# Sheet_Multivibrator.net
KiCad netlist of a schematic drawn in Altium Designer
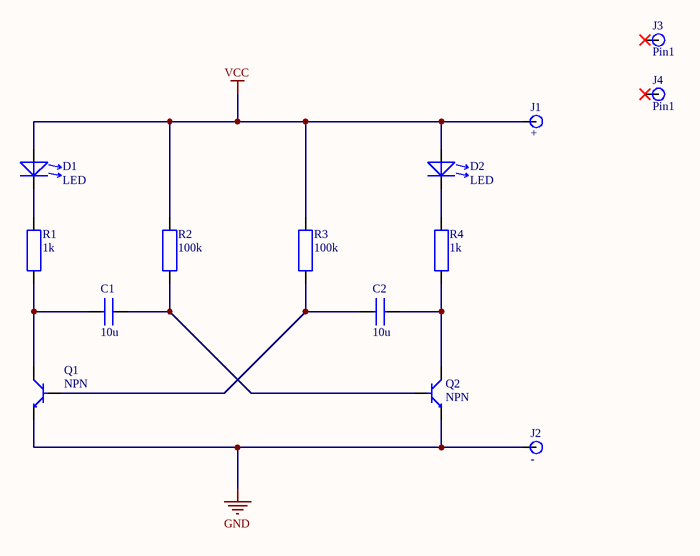
[diagram p0: Sheet_Multivibrator.SchDoc]

(export (version "E")
  (design (tool "Eeschema 10.0.6"))
  (components
    (comp (ref "C1")
      (value "10u")
      (footprint "Capacitor smd 1206")
      (libsource (lib "Schlib1") (part "Capasitor"))
    )
    (comp (ref "C2")
      (value "10u")
      (footprint "Capacitor smd 1206")
      (libsource (lib "Schlib1") (part "Capasitor"))
    )
    (comp (ref "D1") (value "LED") (footprint "LED smd 1206") (libsource (lib "Schlib1") (part "LED")))
    (comp (ref "D2") (value "LED") (footprint "LED smd 1206") (libsource (lib "Schlib1") (part "LED")))
    (comp (ref "J1") (value "+") (footprint "Pin1") (libsource (lib "Schlib1") (part "Pin1")))
    (comp (ref "J2") (value "-") (footprint "Pin1") (libsource (lib "Schlib1") (part "Pin1")))
    (comp (ref "J3") (value "Pin1") (footprint "Pin1") (libsource (lib "Schlib1") (part "Pin1")))
    (comp (ref "J4") (value "Pin1") (footprint "Pin1") (libsource (lib "Schlib1") (part "Pin1")))
    (comp (ref "Q1")
      (value "NPN")
      (footprint "SOT23")
      (libsource (lib "Schlib_Multivibrator") (part "Transistor NPN"))
    )
    (comp (ref "Q2")
      (value "NPN")
      (footprint "SOT23")
      (libsource (lib "Schlib_Multivibrator") (part "Transistor NPN"))
    )
    (comp (ref "R1")
      (value "1k")
      (footprint "Resistor smd 1206")
      (libsource (lib "Schlib1") (part "Resistor"))
    )
    (comp (ref "R2")
      (value "100k")
      (footprint "Resistor smd 1206")
      (libsource (lib "Schlib1") (part "Resistor"))
    )
    (comp (ref "R3")
      (value "100k")
      (footprint "Resistor smd 1206")
      (libsource (lib "Schlib1") (part "Resistor"))
    )
    (comp (ref "R4")
      (value "1k")
      (footprint "Resistor smd 1206")
      (libsource (lib "Schlib1") (part "Resistor"))
    )
  )
  (nets
    (net (code "1") (name "GND") (class "Default")
      (node (ref "J2") (pin "1") (pinfunction "1_1") (pintype "passive"))
      (node (ref "Q1") (pin "E") (pinfunction "E_E") (pintype "passive"))
      (node (ref "Q2") (pin "E") (pinfunction "E_E") (pintype "passive"))
    )
    (net (code "2") (name "Net-(C1-Pad1)") (class "Default")
      (node (ref "C1") (pin "1") (pinfunction "1_1") (pintype "passive"))
      (node (ref "Q1") (pin "C") (pinfunction "C_C") (pintype "passive"))
      (node (ref "R1") (pin "1") (pinfunction "1_1") (pintype "passive"))
    )
    (net (code "3") (name "Net-(C1-Pad2)") (class "Default")
      (node (ref "C1") (pin "2") (pinfunction "2_2") (pintype "passive"))
      (node (ref "Q2") (pin "B") (pinfunction "B_B") (pintype "passive"))
      (node (ref "R2") (pin "1") (pinfunction "1_1") (pintype "passive"))
    )
    (net (code "4") (name "Net-(C2-Pad1)") (class "Default")
      (node (ref "C2") (pin "1") (pinfunction "1_1") (pintype "passive"))
      (node (ref "Q1") (pin "B") (pinfunction "B_B") (pintype "passive"))
      (node (ref "R3") (pin "1") (pinfunction "1_1") (pintype "passive"))
    )
    (net (code "5") (name "Net-(C2-Pad2)") (class "Default")
      (node (ref "C2") (pin "2") (pinfunction "2_2") (pintype "passive"))
      (node (ref "Q2") (pin "C") (pinfunction "C_C") (pintype "passive"))
      (node (ref "R4") (pin "1") (pinfunction "1_1") (pintype "passive"))
    )
    (net (code "6") (name "Net-(D1-PadC)") (class "Default")
      (node (ref "D1") (pin "C") (pinfunction "C_C") (pintype "passive"))
      (node (ref "R1") (pin "2") (pinfunction "2_2") (pintype "passive"))
    )
    (net (code "7") (name "Net-(D2-PadC)") (class "Default")
      (node (ref "D2") (pin "C") (pinfunction "C_C") (pintype "passive"))
      (node (ref "R4") (pin "2") (pinfunction "2_2") (pintype "passive"))
    )
    (net (code "8") (name "VCC") (class "Default")
      (node (ref "D1") (pin "A") (pinfunction "A_A") (pintype "passive"))
      (node (ref "D2") (pin "A") (pinfunction "A_A") (pintype "passive"))
      (node (ref "J1") (pin "1") (pinfunction "1_1") (pintype "passive"))
      (node (ref "R2") (pin "2") (pinfunction "2_2") (pintype "passive"))
      (node (ref "R3") (pin "2") (pinfunction "2_2") (pintype "passive"))
    )
    (net (code "9") (name "unconnected-(J3-Pad1)") (class "Default")
      (node (ref "J3") (pin "1") (pinfunction "1_1") (pintype "passive+no_connect"))
    )
    (net (code "10") (name "unconnected-(J4-Pad1)") (class "Default")
      (node (ref "J4") (pin "1") (pinfunction "1_1") (pintype "passive+no_connect"))
    )
  )
)
